# VibrationMonitorSPT.net
KiCad netlist of a schematic drawn in Altium Designer
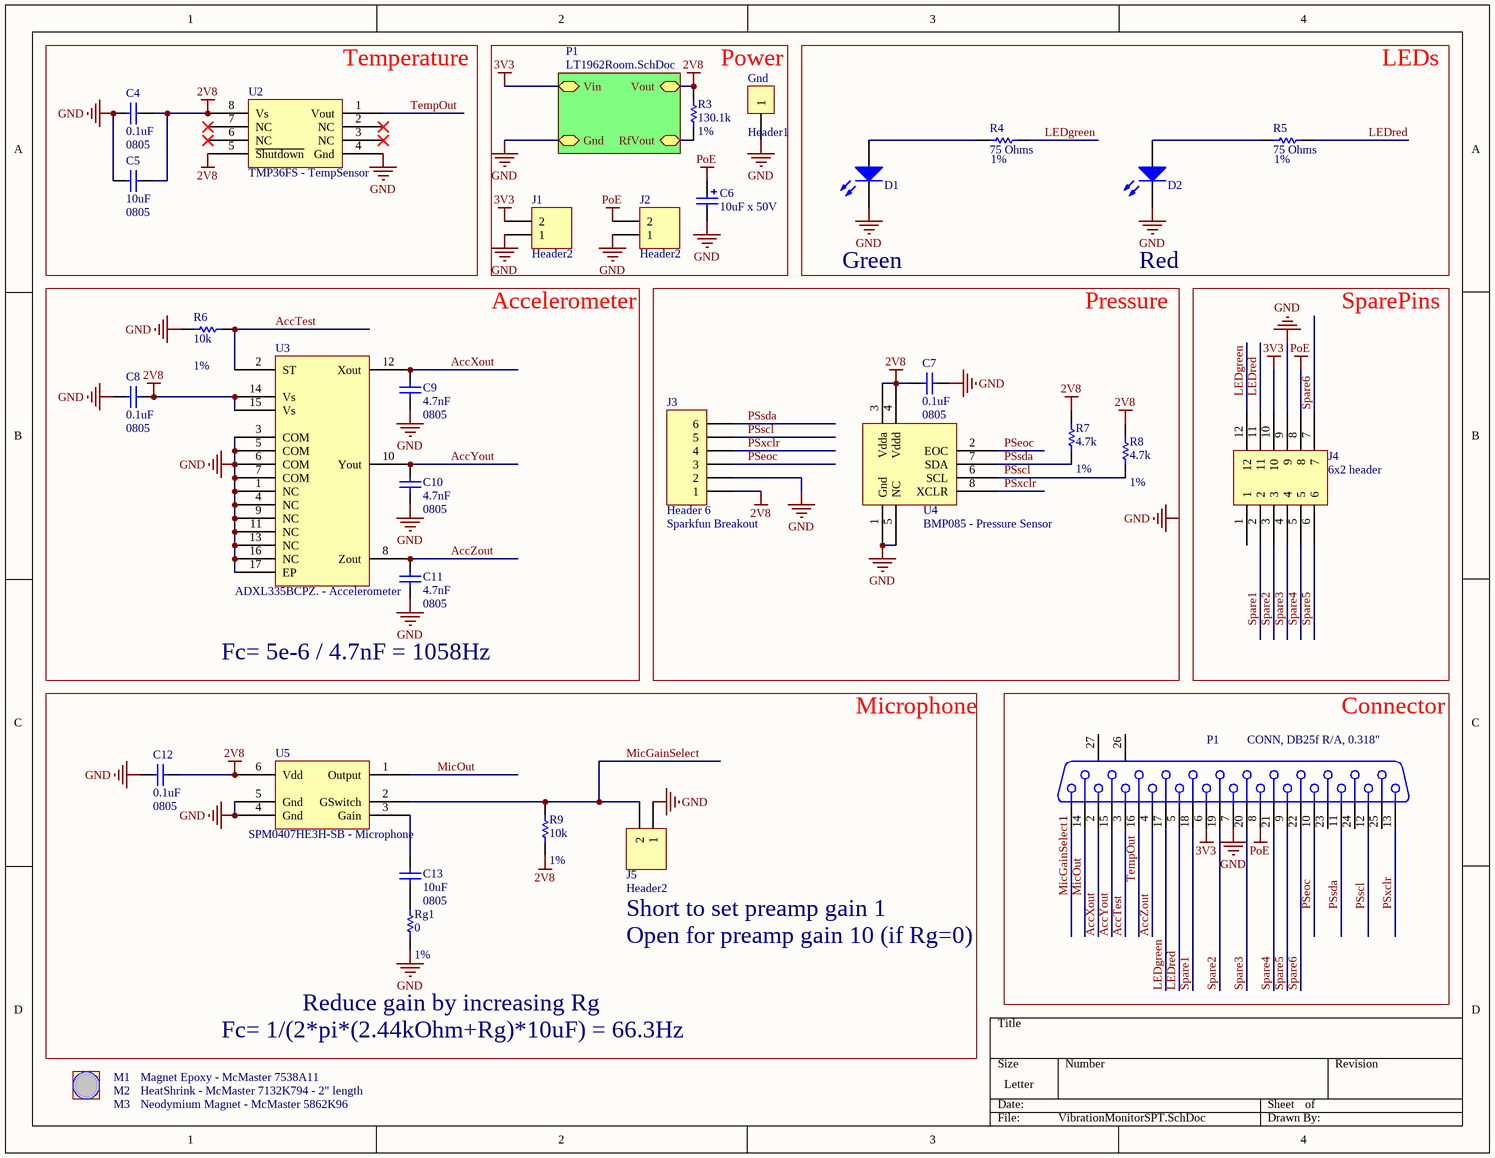
[diagram p0: VibrationMonitorSPT.SchDoc]

(export (version "E")
  (design (tool "Eeschema 10.0.6"))
  (components
    (comp (ref "C4")
      (value "0.1uF")
      (footprint "0805")
      (description "Capacitor, Ceramic, 0603")
      (libsource (lib "AdamsParts") (part "Cap0603"))
    )
    (comp (ref "C5")
      (value "10uF")
      (footprint "0805")
      (description "Capacitor, Ceramic, 0603")
      (libsource (lib "AdamsParts") (part "Cap0603"))
    )
    (comp (ref "C6")
      (value "10uF x 50V")
      (footprint "CC4532-1812")
      (description "CAP POL C4532X5R1C336M")
      (fields (field (name "PUBLISHER") "Altium Limited"))
      (libsource (lib "Miscellaneous Devices") (part "Cap Pol3"))
    )
    (comp (ref "C7")
      (value "0.1uF")
      (footprint "0805")
      (description "Capacitor, Ceramic, 0603")
      (libsource (lib "AdamsParts") (part "Cap0603"))
    )
    (comp (ref "C8")
      (value "0.1uF")
      (footprint "0805")
      (description "Capacitor, Ceramic, 0603")
      (libsource (lib "AdamsParts") (part "Cap0603"))
    )
    (comp (ref "C9")
      (value "4.7nF")
      (footprint "0805")
      (description "Capacitor, Ceramic, 0603")
      (libsource (lib "AdamsParts") (part "Cap0603"))
    )
    (comp (ref "C10")
      (value "4.7nF")
      (footprint "0805")
      (description "Capacitor, Ceramic, 0603")
      (libsource (lib "AdamsParts") (part "Cap0603"))
    )
    (comp (ref "C11")
      (value "4.7nF")
      (footprint "0805")
      (description "Capacitor, Ceramic, 0603")
      (libsource (lib "AdamsParts") (part "Cap0603"))
    )
    (comp (ref "C12")
      (value "0.1uF")
      (footprint "0805")
      (description "Capacitor, Ceramic, 0603")
      (libsource (lib "AdamsParts") (part "Cap0603"))
    )
    (comp (ref "C13")
      (value "10uF")
      (footprint "0805")
      (description "Capacitor, Ceramic, 0603")
      (libsource (lib "AdamsParts") (part "Cap0603"))
    )
    (comp (ref "D1")
      (value "LTST-S270KSKT, Yellow")
      (footprint "LED-S270KGKT")
      (description "LED Side View Yellow 0603")
      (fields (field (name "MANUFACTURER") "Lite-On Inc"))
      (libsource (lib "Semiconductor_Active_Components") (part "LED"))
    )
    (comp (ref "D2")
      (value "LTST-S270KSKT, Yellow")
      (footprint "LED-S270KGKT")
      (description "LED Side View Yellow 0603")
      (fields (field (name "MANUFACTURER") "Lite-On Inc"))
      (libsource (lib "Semiconductor_Active_Components") (part "LED"))
    )
    (comp (ref "Gnd")
      (value "Header1")
      (footprint "HDR1")
      (description "TestPoint1")
      (libsource (lib "AdamsParts") (part "Header1"))
    )
    (comp (ref "J1") (value "Header2") (footprint "HDR1X2") (libsource (lib "") (part "Header2_1")))
    (comp (ref "J2") (value "Header2") (footprint "HDR1X2") (libsource (lib "") (part "Header2_1")))
    (comp (ref "J3")
      (value "Header 6")
      (footprint "HDR1X6")
      (description "Header, 0.1\" 6-Pin straight")
      (fields (field (name "ASSEMBLY") "Sparkfun Breakout") (field (name "PUBLISHER") "*"))
      (libsource (lib "TEMPERATUREREADOUTSYSTEM2") (part "Header 6"))
    )
    (comp (ref "J4")
      (value "6x2 header")
      (footprint "HDR2X6")
      (libsource (lib "AdamsParts") (part "Header6x2"))
    )
    (comp (ref "J5")
      (value "Header2")
      (footprint "HDR1X2")
      (libsource (lib "TEMPERATUREREADOUTSYSTEM2") (part "Header2"))
    )
    (comp (ref "M1")
      (value "Magnet Epoxy - McMaster 7538A11")
      (description "Magnet Epoxy")
      (libsource (lib "AdamsParts") (part "MagnetEpoxy"))
    )
    (comp (ref "M2")
      (value "HeatShrink - McMaster 7132K794 - 2\" length")
      (description "Vibes board Heat Shrink")
      (libsource (lib "AdamsParts") (part "VibesHeatshrink"))
    )
    (comp (ref "M3")
      (value "Neodymium Magnet - McMaster 5862K96")
      (description "Neodymium Magnet")
      (libsource (lib "AdamsParts") (part "MagnetNeodymium"))
    )
    (comp (ref "P1")
      (value "CONN, DB25f R/A, 0.318\"")
      (footprint "DSUB1.385-2H25A")
      (description "Amp 5747846-4 or ITT DBMG25SJA197")
      (fields (field (name "PUBLISHER") "Altium Limited"))
      (libsource (lib "Miscellaneous Connectors") (part "D Connector 25"))
    )
    (comp (ref "R3")
      (value "130.1k")
      (footprint "0805")
      (description "Resistor")
      (fields (field (name "PARAM") "1%"))
      (libsource (lib "AdamsParts") (part "Res0603"))
    )
    (comp (ref "R4")
      (value "75 Ohms")
      (footprint "0805")
      (description "Resistor")
      (fields (field (name "PARAM") "1%"))
      (libsource (lib "AdamsParts") (part "Res0603"))
    )
    (comp (ref "R5")
      (value "75 Ohms")
      (footprint "0805")
      (description "Resistor")
      (fields (field (name "PARAM") "1%"))
      (libsource (lib "AdamsParts") (part "Res0603"))
    )
    (comp (ref "R6")
      (value "10k")
      (footprint "0805")
      (description "Resistor")
      (fields (field (name "PARAM") "1%"))
      (libsource (lib "AdamsParts") (part "Res0603"))
    )
    (comp (ref "R7")
      (value "4.7k")
      (footprint "0603")
      (description "Resistor")
      (fields (field (name "PARAM") "1%"))
      (libsource (lib "AdamsParts") (part "Res0603"))
    )
    (comp (ref "R8")
      (value "4.7k")
      (footprint "0603")
      (description "Resistor")
      (fields (field (name "PARAM") "1%"))
      (libsource (lib "AdamsParts") (part "Res0603"))
    )
    (comp (ref "R9")
      (value "10k")
      (footprint "0603")
      (description "Resistor")
      (fields (field (name "PARAM") "1%"))
      (libsource (lib "AdamsParts") (part "Res0603"))
    )
    (comp (ref "Rg1")
      (value "0")
      (footprint "0805")
      (description "Resistor")
      (fields (field (name "PARAM") "1%"))
      (libsource (lib "AdamsParts") (part "Res0603"))
    )
    (comp (ref "U2")
      (value "TMP36FS - TempSensor")
      (footprint "SO8/L200")
      (libsource (lib "AdamsParts") (part "TMP36FS"))
    )
    (comp (ref "U3")
      (value "ADXL335BCPZ. - Accelerometer")
      (footprint "ADXL335")
      (libsource (lib "AdamsParts") (part "ADXL335"))
    )
    (comp (ref "U4")
      (value "BMP085 - Pressure Sensor")
      (footprint "BMP085")
      (libsource (lib "AdamsParts") (part "BMP085"))
    )
    (comp (ref "U5")
      (value "SPM0407HE3H-SB - Microphone")
      (footprint "SPM0407HE3H-SB")
      (libsource (lib "AdamsParts") (part "SPM0407HE3H-SB"))
    )
  )
  (nets
    (net (code "1") (name "/AccTest") (class "Default")
      (node (ref "P1") (pin "3") (pinfunction "3_3") (pintype "passive"))
      (node (ref "R6") (pin "1") (pinfunction "1_1") (pintype "passive"))
      (node (ref "U3") (pin "2") (pinfunction "ST_2") (pintype "passive"))
    )
    (net (code "2") (name "/AccXout") (class "Default")
      (node (ref "C9") (pin "2") (pinfunction "2_2") (pintype "passive"))
      (node (ref "P1") (pin "2") (pinfunction "2_2") (pintype "passive"))
      (node (ref "U3") (pin "12") (pinfunction "Xout_12") (pintype "passive"))
    )
    (net (code "3") (name "/AccYout") (class "Default")
      (node (ref "C10") (pin "2") (pinfunction "2_2") (pintype "passive"))
      (node (ref "P1") (pin "15") (pinfunction "15_15") (pintype "passive"))
      (node (ref "U3") (pin "10") (pinfunction "Yout_10") (pintype "passive"))
    )
    (net (code "4") (name "/AccZout") (class "Default")
      (node (ref "C11") (pin "2") (pinfunction "2_2") (pintype "passive"))
      (node (ref "P1") (pin "4") (pinfunction "4_4") (pintype "passive"))
      (node (ref "U3") (pin "8") (pinfunction "Zout_8") (pintype "passive"))
    )
    (net (code "5") (name "/LEDgreen") (class "Default")
      (node (ref "J4") (pin "12") (pinfunction "12_12") (pintype "passive"))
      (node (ref "P1") (pin "17") (pinfunction "17_17") (pintype "passive"))
      (node (ref "R4") (pin "2") (pinfunction "2_2") (pintype "passive"))
    )
    (net (code "6") (name "/LEDred") (class "Default")
      (node (ref "J4") (pin "11") (pinfunction "11_11") (pintype "passive"))
      (node (ref "P1") (pin "5") (pinfunction "5_5") (pintype "passive"))
      (node (ref "R5") (pin "2") (pinfunction "2_2") (pintype "passive"))
    )
    (net (code "7") (name "/MicGainSelect") (class "Default")
      (node (ref "J5") (pin "2") (pinfunction "2_2") (pintype "passive"))
      (node (ref "P1") (pin "1") (pinfunction "1_1") (pintype "passive"))
      (node (ref "R9") (pin "2") (pinfunction "2_2") (pintype "passive"))
      (node (ref "U5") (pin "2") (pinfunction "GSwitch_2") (pintype "passive"))
    )
    (net (code "8") (name "/MicOut") (class "Default")
      (node (ref "P1") (pin "14") (pinfunction "14_14") (pintype "passive"))
      (node (ref "U5") (pin "1") (pinfunction "Output_1") (pintype "passive"))
    )
    (net (code "9") (name "/PSeoc") (class "Default")
      (node (ref "J3") (pin "3") (pinfunction "3_3") (pintype "passive"))
      (node (ref "P1") (pin "10") (pinfunction "10_10") (pintype "passive"))
      (node (ref "U4") (pin "2") (pinfunction "EOC_2") (pintype "passive"))
    )
    (net (code "10") (name "/PSscl") (class "Default")
      (node (ref "J3") (pin "5") (pinfunction "5_5") (pintype "passive"))
      (node (ref "P1") (pin "12") (pinfunction "12_12") (pintype "passive"))
      (node (ref "R8") (pin "2") (pinfunction "2_2") (pintype "passive"))
      (node (ref "U4") (pin "6") (pinfunction "SCL_6") (pintype "passive"))
    )
    (net (code "11") (name "/PSsda") (class "Default")
      (node (ref "J3") (pin "6") (pinfunction "6_6") (pintype "passive"))
      (node (ref "P1") (pin "11") (pinfunction "11_11") (pintype "passive"))
      (node (ref "R7") (pin "2") (pinfunction "2_2") (pintype "passive"))
      (node (ref "U4") (pin "7") (pinfunction "SDA_7") (pintype "passive"))
    )
    (net (code "12") (name "/PSxclr") (class "Default")
      (node (ref "J3") (pin "4") (pinfunction "4_4") (pintype "passive"))
      (node (ref "P1") (pin "13") (pinfunction "13_13") (pintype "passive"))
      (node (ref "U4") (pin "8") (pinfunction "XCLR_8") (pintype "passive"))
    )
    (net (code "13") (name "/RfVout") (class "Default")
      (node (ref "R3") (pin "1") (pinfunction "1_1") (pintype "passive"))
    )
    (net (code "14") (name "/Spare1") (class "Default")
      (node (ref "J4") (pin "2") (pinfunction "2_2") (pintype "passive"))
      (node (ref "P1") (pin "18") (pinfunction "18_18") (pintype "passive"))
    )
    (net (code "15") (name "/Spare2") (class "Default")
      (node (ref "J4") (pin "3") (pinfunction "3_3") (pintype "passive"))
      (node (ref "P1") (pin "19") (pinfunction "19_19") (pintype "passive"))
    )
    (net (code "16") (name "/Spare3") (class "Default")
      (node (ref "J4") (pin "4") (pinfunction "4_4") (pintype "passive"))
      (node (ref "P1") (pin "20") (pinfunction "20_20") (pintype "passive"))
    )
    (net (code "17") (name "/Spare4") (class "Default")
      (node (ref "J4") (pin "5") (pinfunction "5_5") (pintype "passive"))
      (node (ref "P1") (pin "21") (pinfunction "21_21") (pintype "passive"))
    )
    (net (code "18") (name "/Spare5") (class "Default")
      (node (ref "J4") (pin "6") (pinfunction "6_6") (pintype "passive"))
      (node (ref "P1") (pin "9") (pinfunction "9_9") (pintype "passive"))
    )
    (net (code "19") (name "/Spare6") (class "Default")
      (node (ref "J4") (pin "7") (pinfunction "7_7") (pintype "passive"))
      (node (ref "P1") (pin "22") (pinfunction "22_22") (pintype "passive"))
    )
    (net (code "20") (name "/TempOut") (class "Default")
      (node (ref "P1") (pin "16") (pinfunction "16_16") (pintype "passive"))
      (node (ref "U2") (pin "1") (pinfunction "Vout_1") (pintype "passive"))
    )
    (net (code "21") (name "2V8") (class "Default")
      (node (ref "C12") (pin "1") (pinfunction "1_1") (pintype "passive"))
      (node (ref "C4") (pin "1") (pinfunction "1_1") (pintype "passive"))
      (node (ref "C5") (pin "1") (pinfunction "1_1") (pintype "passive"))
      (node (ref "C7") (pin "2") (pinfunction "2_2") (pintype "passive"))
      (node (ref "C8") (pin "1") (pinfunction "1_1") (pintype "passive"))
      (node (ref "J3") (pin "1") (pinfunction "1_1") (pintype "passive"))
      (node (ref "R3") (pin "2") (pinfunction "2_2") (pintype "passive"))
      (node (ref "R7") (pin "1") (pinfunction "1_1") (pintype "passive"))
      (node (ref "R8") (pin "1") (pinfunction "1_1") (pintype "passive"))
      (node (ref "R9") (pin "1") (pinfunction "1_1") (pintype "passive"))
      (node (ref "U2") (pin "5") (pinfunction "~{Shutdown}_5") (pintype "passive"))
      (node (ref "U2") (pin "8") (pinfunction "Vs_8") (pintype "passive"))
      (node (ref "U3") (pin "14") (pinfunction "Vs_14") (pintype "passive"))
      (node (ref "U3") (pin "15") (pinfunction "Vs_15") (pintype "passive"))
      (node (ref "U4") (pin "3") (pinfunction "Vdda_3") (pintype "passive"))
      (node (ref "U4") (pin "4") (pinfunction "Vddd_4") (pintype "passive"))
      (node (ref "U5") (pin "6") (pinfunction "Vdd_6") (pintype "passive"))
    )
    (net (code "22") (name "3V3") (class "Default")
      (node (ref "J1") (pin "2") (pinfunction "2_2") (pintype "passive"))
      (node (ref "J4") (pin "10") (pinfunction "10_10") (pintype "passive"))
      (node (ref "P1") (pin "6") (pinfunction "6_6") (pintype "passive"))
    )
    (net (code "23") (name "GND") (class "Default")
      (node (ref "C10") (pin "1") (pinfunction "1_1") (pintype "passive"))
      (node (ref "C11") (pin "1") (pinfunction "1_1") (pintype "passive"))
      (node (ref "C12") (pin "2") (pinfunction "2_2") (pintype "passive"))
      (node (ref "C4") (pin "2") (pinfunction "2_2") (pintype "passive"))
      (node (ref "C5") (pin "2") (pinfunction "2_2") (pintype "passive"))
      (node (ref "C6") (pin "2") (pinfunction "2_2") (pintype "passive"))
      (node (ref "C7") (pin "1") (pinfunction "1_1") (pintype "passive"))
      (node (ref "C8") (pin "2") (pinfunction "2_2") (pintype "passive"))
      (node (ref "C9") (pin "1") (pinfunction "1_1") (pintype "passive"))
      (node (ref "D1") (pin "2") (pinfunction "K_2") (pintype "passive"))
      (node (ref "D2") (pin "2") (pinfunction "K_2") (pintype "passive"))
      (node (ref "Gnd") (pin "1") (pinfunction "1_1") (pintype "passive"))
      (node (ref "J1") (pin "1") (pinfunction "1_1") (pintype "passive"))
      (node (ref "J2") (pin "1") (pinfunction "1_1") (pintype "passive"))
      (node (ref "J3") (pin "2") (pinfunction "2_2") (pintype "passive"))
      (node (ref "J4") (pin "9") (pinfunction "9_9") (pintype "passive"))
      (node (ref "J5") (pin "1") (pinfunction "1_1") (pintype "passive"))
      (node (ref "P1") (pin "7") (pinfunction "7_7") (pintype "passive"))
      (node (ref "R6") (pin "2") (pinfunction "2_2") (pintype "passive"))
      (node (ref "Rg1") (pin "1") (pinfunction "1_1") (pintype "passive"))
      (node (ref "U2") (pin "4") (pinfunction "Gnd_4") (pintype "passive"))
      (node (ref "U3") (pin "1") (pinfunction "NC_1") (pintype "passive"))
      (node (ref "U3") (pin "11") (pinfunction "NC_11") (pintype "passive"))
      (node (ref "U3") (pin "13") (pinfunction "NC_13") (pintype "passive"))
      (node (ref "U3") (pin "16") (pinfunction "NC_16") (pintype "passive"))
      (node (ref "U3") (pin "17") (pinfunction "EP_17") (pintype "passive"))
      (node (ref "U3") (pin "3") (pinfunction "COM_3") (pintype "passive"))
      (node (ref "U3") (pin "4") (pinfunction "NC_4") (pintype "passive"))
      (node (ref "U3") (pin "5") (pinfunction "COM_5") (pintype "passive"))
      (node (ref "U3") (pin "6") (pinfunction "COM_6") (pintype "passive"))
      (node (ref "U3") (pin "7") (pinfunction "COM_7") (pintype "passive"))
      (node (ref "U3") (pin "9") (pinfunction "NC_9") (pintype "passive"))
      (node (ref "U4") (pin "1") (pinfunction "Gnd_1") (pintype "passive"))
      (node (ref "U4") (pin "5") (pinfunction "NC_5") (pintype "passive"))
      (node (ref "U5") (pin "4") (pinfunction "Gnd_4") (pintype "passive"))
      (node (ref "U5") (pin "5") (pinfunction "Gnd_5") (pintype "passive"))
    )
    (net (code "24") (name "Net-(C13-Pad2)") (class "Default")
      (node (ref "C13") (pin "2") (pinfunction "2_2") (pintype "passive"))
      (node (ref "Rg1") (pin "2") (pinfunction "2_2") (pintype "passive"))
    )
    (net (code "25") (name "Net-(D1-A)") (class "Default")
      (node (ref "D1") (pin "1") (pinfunction "A_1") (pintype "passive"))
      (node (ref "R4") (pin "1") (pinfunction "1_1") (pintype "passive"))
    )
    (net (code "26") (name "Net-(D2-A)") (class "Default")
      (node (ref "D2") (pin "1") (pinfunction "A_1") (pintype "passive"))
      (node (ref "R5") (pin "1") (pinfunction "1_1") (pintype "passive"))
    )
    (net (code "27") (name "Net-(U5-Gain)") (class "Default")
      (node (ref "C13") (pin "1") (pinfunction "1_1") (pintype "passive"))
      (node (ref "U5") (pin "3") (pinfunction "Gain_3") (pintype "passive"))
    )
    (net (code "28") (name "PoE") (class "Default")
      (node (ref "C6") (pin "1") (pinfunction "1_1") (pintype "passive"))
      (node (ref "J2") (pin "2") (pinfunction "2_2") (pintype "passive"))
      (node (ref "J4") (pin "8") (pinfunction "8_8") (pintype "passive"))
      (node (ref "P1") (pin "8") (pinfunction "8_8") (pintype "passive"))
    )
    (net (code "29") (name "unconnected-(J4-Pad1)") (class "Default")
      (node (ref "J4") (pin "1") (pinfunction "1_1") (pintype "passive"))
    )
    (net (code "30") (name "unconnected-(P1-MH1-Pad26)") (class "Default")
      (node (ref "P1") (pin "26") (pinfunction "MH1_26") (pintype "passive"))
    )
    (net (code "31") (name "unconnected-(P1-MH2-Pad27)") (class "Default")
      (node (ref "P1") (pin "27") (pinfunction "MH2_27") (pintype "passive"))
    )
    (net (code "32") (name "unconnected-(P1-Pad23)") (class "Default")
      (node (ref "P1") (pin "23") (pinfunction "23_23") (pintype "passive"))
    )
    (net (code "33") (name "unconnected-(P1-Pad24)") (class "Default")
      (node (ref "P1") (pin "24") (pinfunction "24_24") (pintype "passive"))
    )
    (net (code "34") (name "unconnected-(P1-Pad25)") (class "Default")
      (node (ref "P1") (pin "25") (pinfunction "25_25") (pintype "passive"))
    )
    (net (code "35") (name "unconnected-(U2-NC-Pad2)") (class "Default")
      (node (ref "U2") (pin "2") (pinfunction "NC_2") (pintype "passive+no_connect"))
    )
    (net (code "36") (name "unconnected-(U2-NC-Pad3)") (class "Default")
      (node (ref "U2") (pin "3") (pinfunction "NC_3") (pintype "passive+no_connect"))
    )
    (net (code "37") (name "unconnected-(U2-NC-Pad6)") (class "Default")
      (node (ref "U2") (pin "6") (pinfunction "NC_6") (pintype "passive+no_connect"))
    )
    (net (code "38") (name "unconnected-(U2-NC-Pad7)") (class "Default")
      (node (ref "U2") (pin "7") (pinfunction "NC_7") (pintype "passive+no_connect"))
    )
  )
)
